# SCH_pcb-card_2025-04-23.net
KiCad netlist of a schematic drawn in EasyEDA
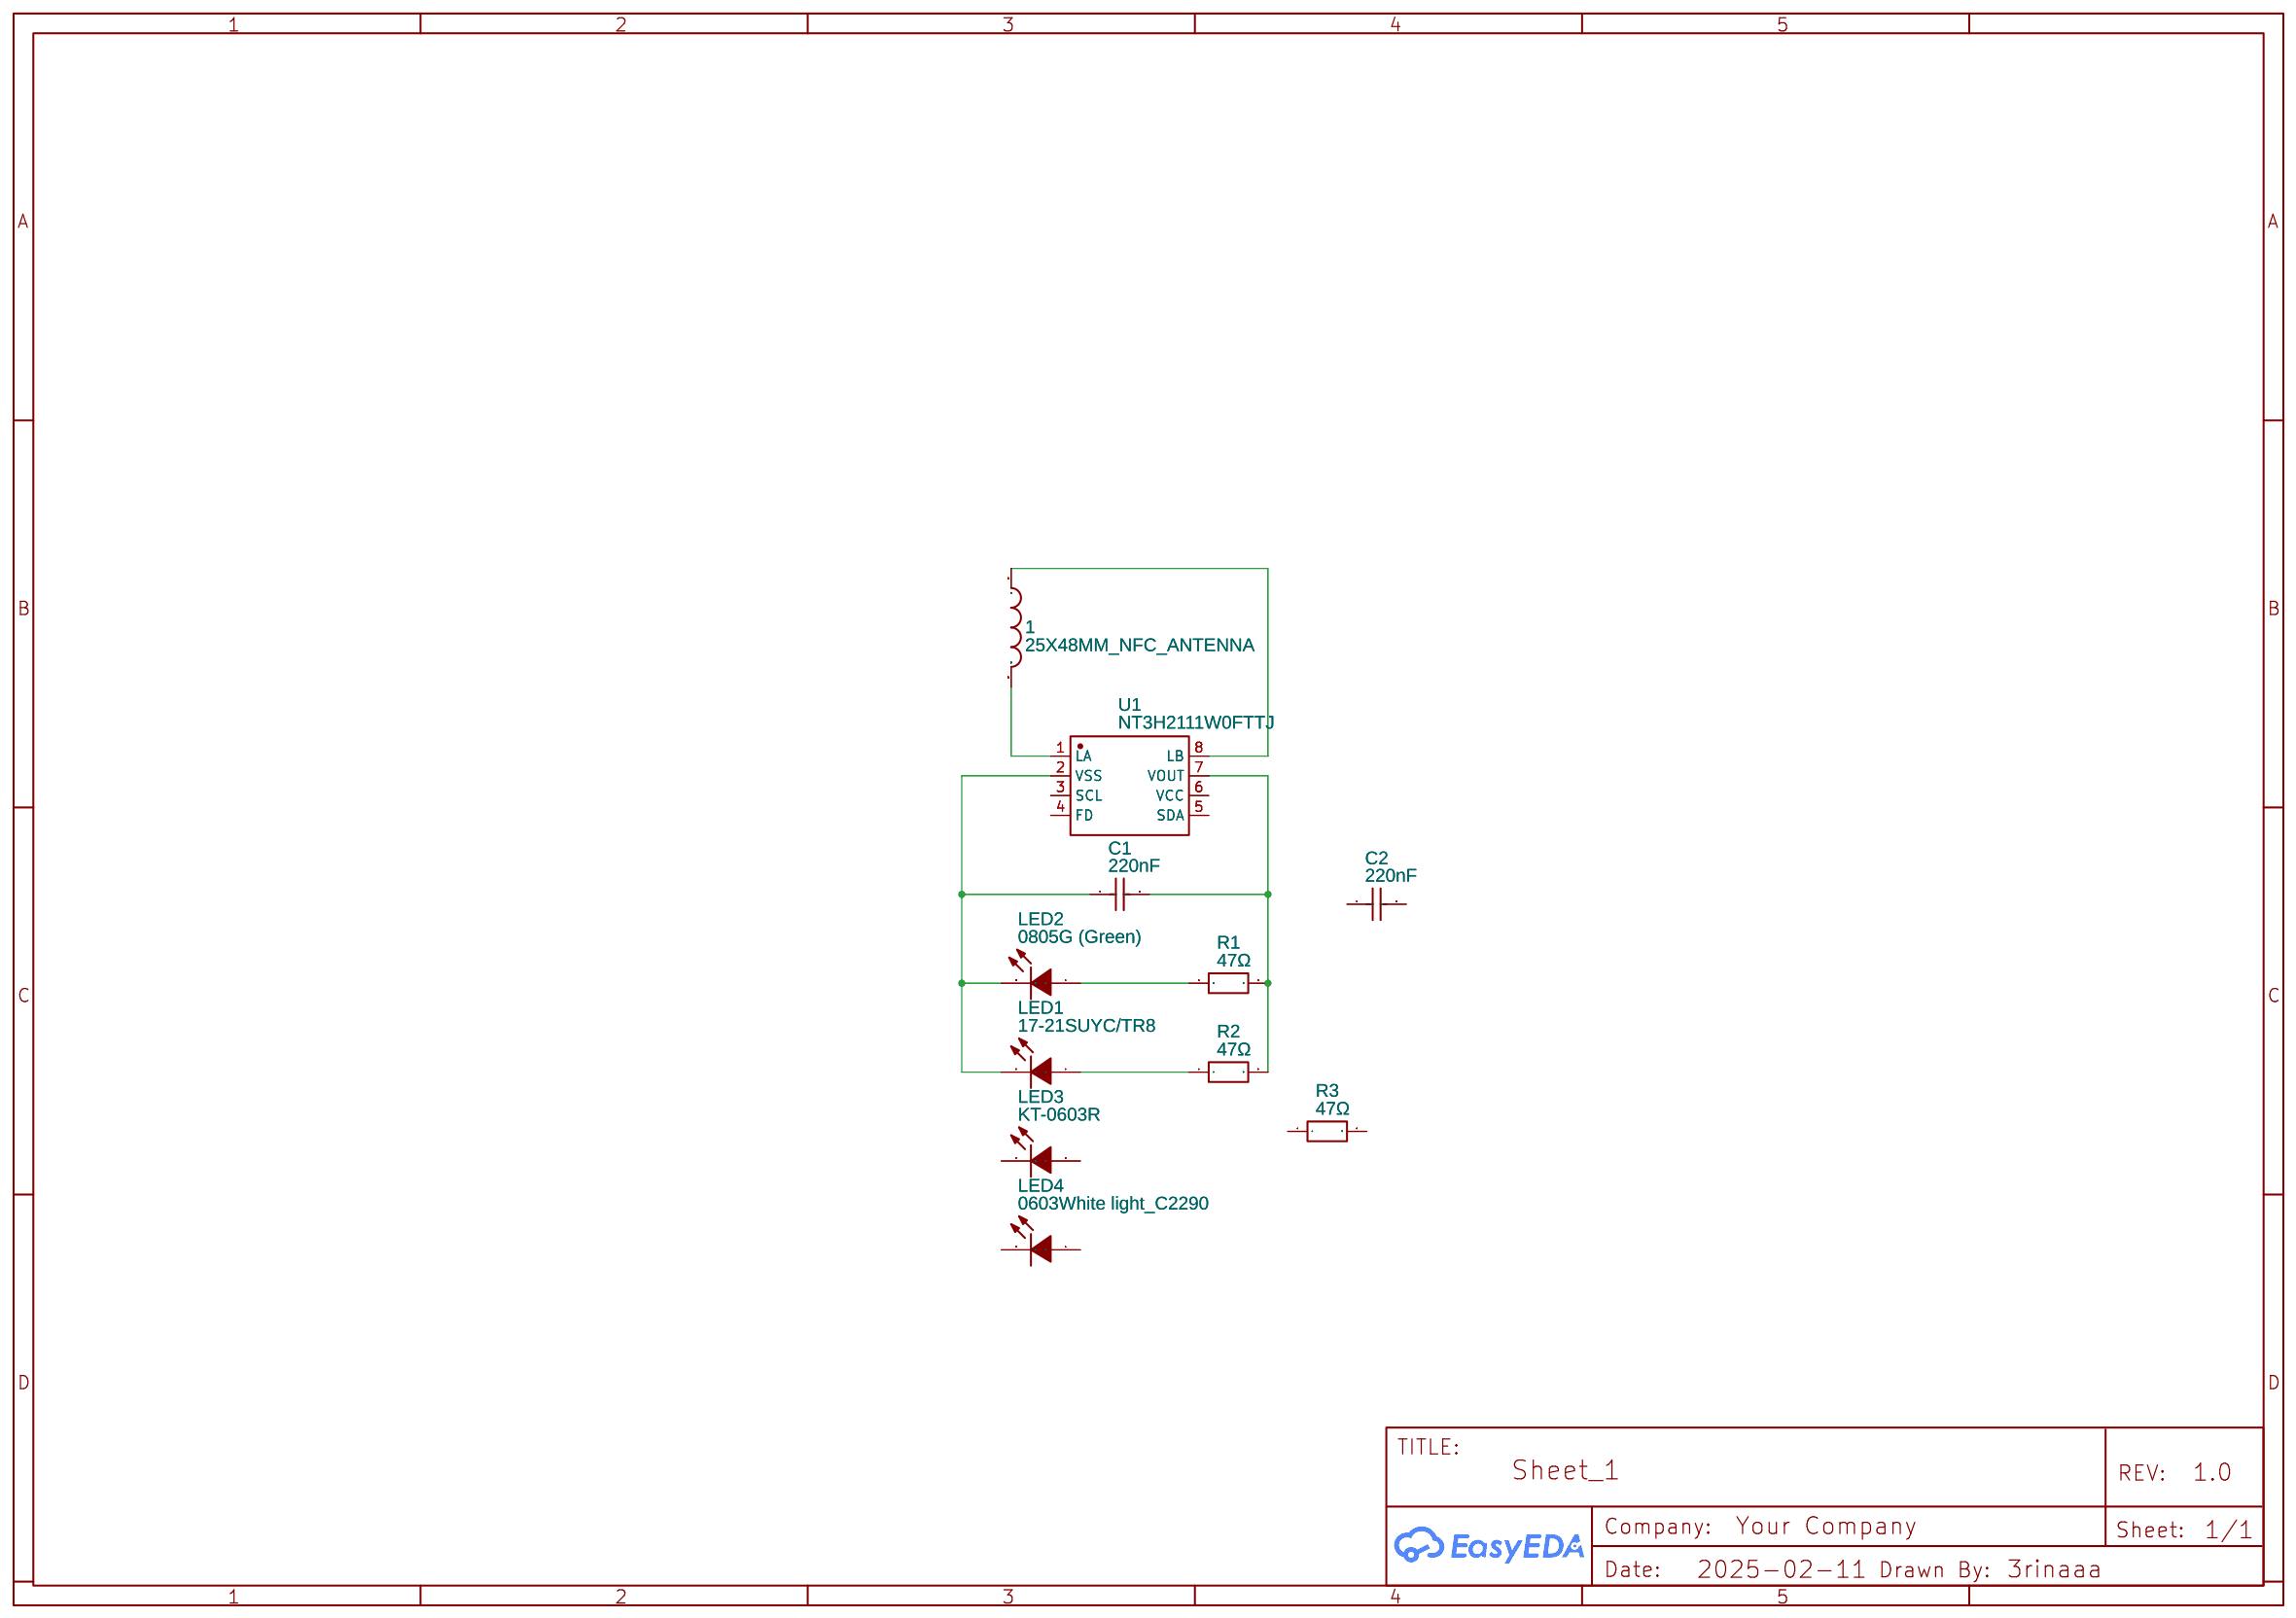
[diagram p0: schematic sheet]

(export (version "E")
  (design (tool "Eeschema 10.0.6"))
  (components
    (comp (ref "1") (value "25X48MM_NFC_ANTENNA") (libsource (lib "") (part "25X48MM_NFC_ANTENNA")))
    (comp (ref "C1")
      (value "220nF")
      (fields
        (field (name "Manufacturer Part") "CL05B224KO5NNNC")
        (field (name "Manufacturer") "SAMSUNG(三星)")
      )
      (libsource (lib "") (part "CL05B224KO5NNNC"))
    )
    (comp (ref "C2")
      (value "220nF")
      (fields
        (field (name "Manufacturer Part") "CL05B224KO5NNNC")
        (field (name "Manufacturer") "SAMSUNG(三星)")
      )
      (libsource (lib "") (part "CL05B224KO5NNNC"))
    )
    (comp (ref "LED1")
      (value "17-21SUYC/TR8")
      (fields (field (name "Manufacturer Part") "KT-0805黄灯") (field (name "Manufacturer") "KENTO"))
      (libsource (lib "") (part "17-21SUYC/TR8"))
    )
    (comp (ref "LED2")
      (value "0805G (Green)")
      (fields (field (name "Manufacturer Part") "KT-0805G") (field (name "Manufacturer") "KENTO"))
      (libsource (lib "") (part "0805G (Green)"))
    )
    (comp (ref "LED3")
      (value "KT-0603R")
      (fields (field (name "Manufacturer") "KENTO"))
      (libsource (lib "") (part "KT-0603R"))
    )
    (comp (ref "LED4")
      (value "0603White light_C2290")
      (fields (field (name "Manufacturer Part") "KT-0603W") (field (name "Manufacturer") "KENTO"))
      (libsource (lib "") (part "0603White light_C2290"))
    )
    (comp (ref "R1")
      (value "47Ω")
      (fields (field (name "Manufacturer Part") "FRC0603J470 TS") (field (name "Manufacturer") "FOJAN(富捷)"))
      (libsource (lib "") (part "FRC0603J470 TS"))
    )
    (comp (ref "R2")
      (value "47Ω")
      (fields (field (name "Manufacturer Part") "FRC0603J470 TS") (field (name "Manufacturer") "FOJAN(富捷)"))
      (libsource (lib "") (part "FRC0603J470 TS"))
    )
    (comp (ref "R3")
      (value "47Ω")
      (fields (field (name "Manufacturer Part") "FRC0603J470 TS") (field (name "Manufacturer") "FOJAN(富捷)"))
      (libsource (lib "") (part "FRC0603J470 TS"))
    )
    (comp (ref "U1")
      (value "NT3H2111W0FTTJ")
      (fields (field (name "Manufacturer") "NXP(恩智浦)"))
      (libsource (lib "") (part "NT3H2111W0FTTJ"))
    )
  )
  (nets
    (net (code "1") (name "Net-(LED1-+)") (class "Default")
      (node (ref "LED1") (pin "1") (pinfunction "+_1") (pintype "unspecified"))
      (node (ref "R2") (pin "1") (pinfunction "1_1") (pintype "unspecified"))
    )
    (net (code "2") (name "Net-(LED1--)") (class "Default")
      (node (ref "C1") (pin "1") (pinfunction "1_1") (pintype "input"))
      (node (ref "LED1") (pin "2") (pinfunction "-_2") (pintype "unspecified"))
      (node (ref "LED2") (pin "2") (pinfunction "K_2") (pintype "unspecified"))
      (node (ref "U1") (pin "2") (pinfunction "VSS_2") (pintype "unspecified"))
    )
    (net (code "3") (name "Net-(LED2-A)") (class "Default")
      (node (ref "LED2") (pin "1") (pinfunction "A_1") (pintype "unspecified"))
      (node (ref "R1") (pin "1") (pinfunction "1_1") (pintype "unspecified"))
    )
    (net (code "4") (name "Net-(U1-LA)") (class "Default")
      (node (ref "1") (pin "P$2") (pinfunction "P$2_P$2") (pintype "bidirectional"))
      (node (ref "U1") (pin "1") (pinfunction "LA_1") (pintype "unspecified"))
    )
    (net (code "5") (name "Net-(U1-LB)") (class "Default")
      (node (ref "1") (pin "P$1") (pinfunction "P$1_P$1") (pintype "bidirectional"))
      (node (ref "U1") (pin "8") (pinfunction "LB_8") (pintype "unspecified"))
    )
    (net (code "6") (name "Net-(U1-VOUT)") (class "Default")
      (node (ref "C1") (pin "2") (pinfunction "2_2") (pintype "input"))
      (node (ref "R1") (pin "2") (pinfunction "2_2") (pintype "unspecified"))
      (node (ref "R2") (pin "2") (pinfunction "2_2") (pintype "unspecified"))
      (node (ref "U1") (pin "7") (pinfunction "VOUT_7") (pintype "unspecified"))
    )
    (net (code "7") (name "unconnected-(C2-Pad1)") (class "Default")
      (node (ref "C2") (pin "1") (pinfunction "1_1") (pintype "input"))
    )
    (net (code "8") (name "unconnected-(C2-Pad2)") (class "Default")
      (node (ref "C2") (pin "2") (pinfunction "2_2") (pintype "input"))
    )
    (net (code "9") (name "unconnected-(LED3-A-Pad2)") (class "Default")
      (node (ref "LED3") (pin "2") (pinfunction "A_2") (pintype "unspecified"))
    )
    (net (code "10") (name "unconnected-(LED3-K-Pad1)") (class "Default")
      (node (ref "LED3") (pin "1") (pinfunction "K_1") (pintype "unspecified"))
    )
    (net (code "11") (name "unconnected-(LED4-A-Pad1)") (class "Default")
      (node (ref "LED4") (pin "1") (pinfunction "A_1") (pintype "unspecified"))
    )
    (net (code "12") (name "unconnected-(LED4-K-Pad2)") (class "Default")
      (node (ref "LED4") (pin "2") (pinfunction "K_2") (pintype "unspecified"))
    )
    (net (code "13") (name "unconnected-(R3-Pad1)") (class "Default")
      (node (ref "R3") (pin "1") (pinfunction "1_1") (pintype "unspecified"))
    )
    (net (code "14") (name "unconnected-(R3-Pad2)") (class "Default")
      (node (ref "R3") (pin "2") (pinfunction "2_2") (pintype "unspecified"))
    )
    (net (code "15") (name "unconnected-(U1-FD-Pad4)") (class "Default")
      (node (ref "U1") (pin "4") (pinfunction "FD_4") (pintype "unspecified"))
    )
    (net (code "16") (name "unconnected-(U1-SCL-Pad3)") (class "Default")
      (node (ref "U1") (pin "3") (pinfunction "SCL_3") (pintype "unspecified"))
    )
    (net (code "17") (name "unconnected-(U1-SDA-Pad5)") (class "Default")
      (node (ref "U1") (pin "5") (pinfunction "SDA_5") (pintype "unspecified"))
    )
    (net (code "18") (name "unconnected-(U1-VCC-Pad6)") (class "Default")
      (node (ref "U1") (pin "6") (pinfunction "VCC_6") (pintype "unspecified"))
    )
  )
)
